# cpu.net
KiCad netlist of a schematic drawn in Altium Designer
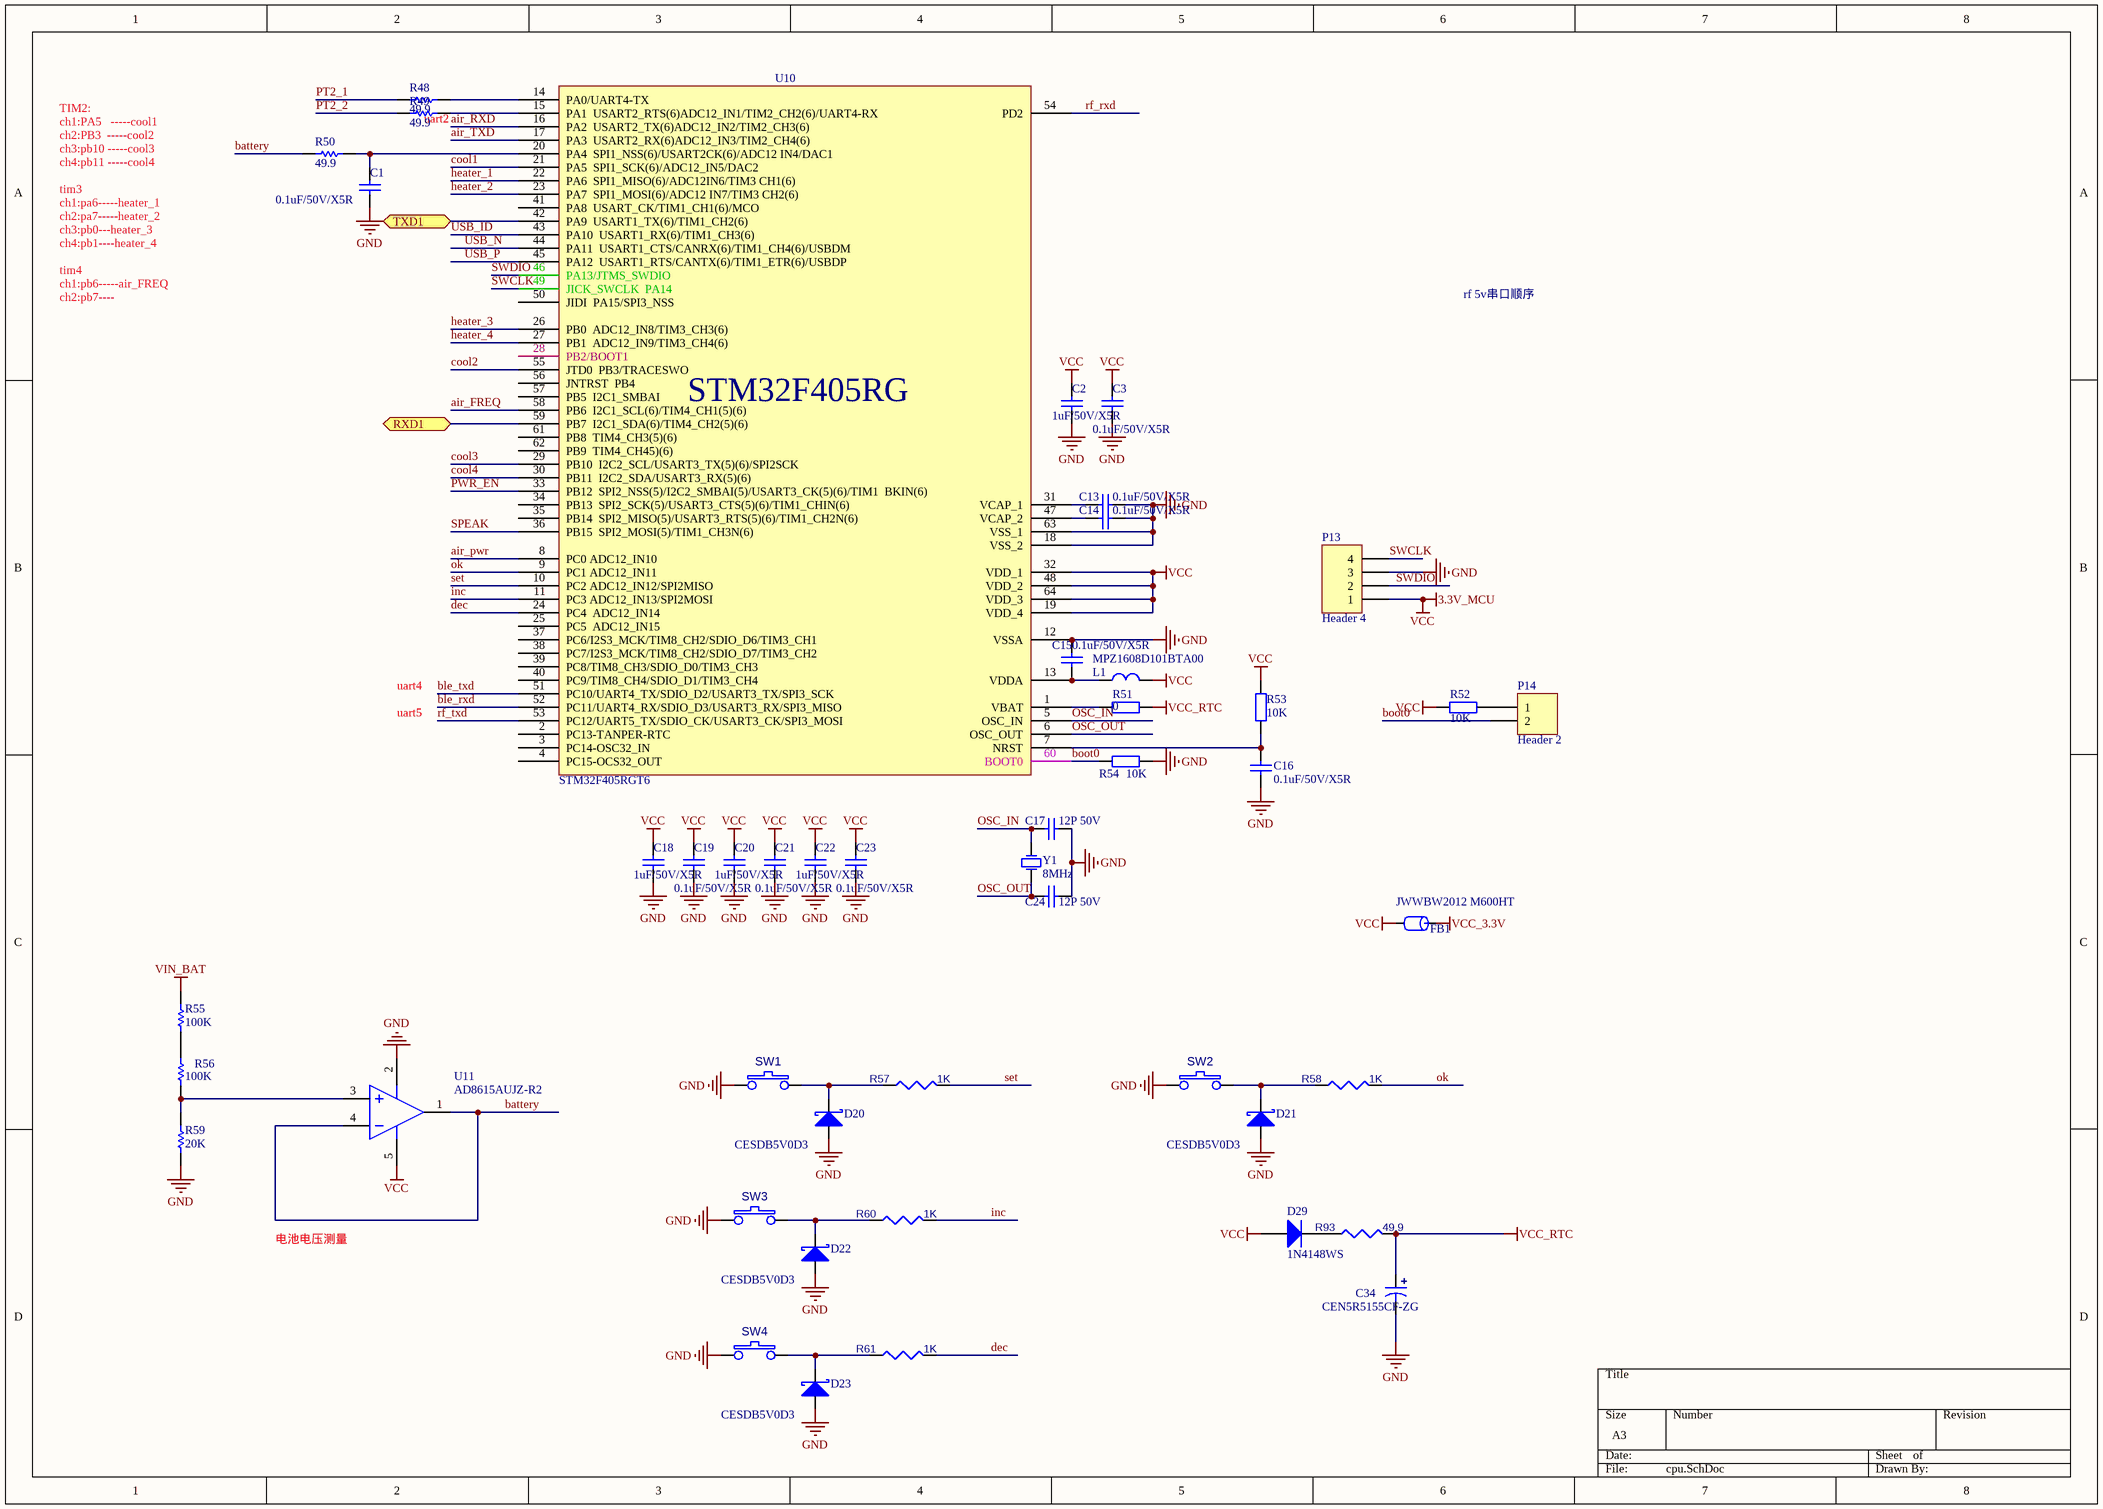
[diagram p0: cpu.SchDoc]

(export (version "E")
  (design (tool "Eeschema 10.0.6"))
  (components
    (comp (ref "C1")
      (value "0.1uF/50V/X5R")
      (footprint "0603C")
      (description "贴片电容 20%")
      (libsource (lib "XiaoyI") (part "CAP4"))
    )
    (comp (ref "C2")
      (value "1uF/50V/X5R")
      (footprint "0603C")
      (description "贴片电容 20%")
      (libsource (lib "XiaoyI") (part "CAP4"))
    )
    (comp (ref "C3")
      (value "0.1uF/50V/X5R")
      (footprint "0603C")
      (description "贴片电容 20%")
      (libsource (lib "XiaoyI") (part "CAP4"))
    )
    (comp (ref "C13")
      (value "0.1uF/50V/X5R")
      (footprint "0603C")
      (description "贴片电容 20%")
      (libsource (lib "XiaoyI") (part "CAP4"))
    )
    (comp (ref "C14")
      (value "0.1uF/50V/X5R")
      (footprint "0603C")
      (description "贴片电容 20%")
      (libsource (lib "XiaoyI") (part "CAP4"))
    )
    (comp (ref "C15")
      (value "0.1uF/50V/X5R")
      (footprint "0603C")
      (description "贴片电容 20%")
      (libsource (lib "XiaoyI") (part "CAP4"))
    )
    (comp (ref "C16")
      (value "0.1uF/50V/X5R")
      (footprint "0603C")
      (description "贴片电容 20%")
      (libsource (lib "XiaoyI") (part "CAP4"))
    )
    (comp (ref "C17")
      (value "12P 50V")
      (footprint "0603C")
      (description "贴片电容 20%")
      (libsource (lib "XiaoyI") (part "CAP4"))
    )
    (comp (ref "C18")
      (value "1uF/50V/X5R")
      (footprint "0603C")
      (description "贴片电容 20%")
      (libsource (lib "XiaoyI") (part "CAP4"))
    )
    (comp (ref "C19")
      (value "0.1uF/50V/X5R")
      (footprint "0603C")
      (description "贴片电容 20%")
      (libsource (lib "XiaoyI") (part "CAP4"))
    )
    (comp (ref "C20")
      (value "1uF/50V/X5R")
      (footprint "0603C")
      (description "贴片电容 20%")
      (libsource (lib "XiaoyI") (part "CAP4"))
    )
    (comp (ref "C21")
      (value "0.1uF/50V/X5R")
      (footprint "0603C")
      (description "贴片电容 20%")
      (libsource (lib "XiaoyI") (part "CAP4"))
    )
    (comp (ref "C22")
      (value "1uF/50V/X5R")
      (footprint "0603C")
      (description "贴片电容 20%")
      (libsource (lib "XiaoyI") (part "CAP4"))
    )
    (comp (ref "C23")
      (value "0.1uF/50V/X5R")
      (footprint "0603C")
      (description "贴片电容 20%")
      (libsource (lib "XiaoyI") (part "CAP4"))
    )
    (comp (ref "C24")
      (value "12P 50V")
      (footprint "0603C")
      (description "贴片电容 20%")
      (libsource (lib "XiaoyI") (part "CAP4"))
    )
    (comp (ref "C34")
      (value "CEN5R5155CF-ZG")
      (footprint "CAP-TH_BD21.0-P5.00-D0.8_CENXXX-CF")
      (description "电解电容")
      (libsource (lib "XiaoyI") (part "CAP2"))
    )
    (comp (ref "D20")
      (value "CESDB5V0D3")
      (footprint "SOD323")
      (description "Schottky Diode")
      (libsource (lib "*") (part "DIODE S"))
    )
    (comp (ref "D21")
      (value "CESDB5V0D3")
      (footprint "SOD323")
      (description "Schottky Diode")
      (libsource (lib "*") (part "DIODE S"))
    )
    (comp (ref "D22")
      (value "CESDB5V0D3")
      (footprint "SOD323")
      (description "Schottky Diode")
      (libsource (lib "*") (part "DIODE S"))
    )
    (comp (ref "D23")
      (value "CESDB5V0D3")
      (footprint "SOD323")
      (description "Schottky Diode")
      (libsource (lib "*") (part "DIODE S"))
    )
    (comp (ref "D29") (value "1N4148WS") (footprint "SOD323") (libsource (lib "Sch_library") (part "DIODE")))
    (comp (ref "FB1")
      (value "JWWBW2012 M600HT")
      (footprint "0805CZ")
      (libsource (lib "Schlib_20110825") (part "FB"))
    )
    (comp (ref "L1")
      (value "MPZ1608D101BTA00")
      (footprint "0603R")
      (description "磁珠电感 100R 100MHz")
      (libsource (lib "XiaoyI") (part "CIZHU1"))
    )
    (comp (ref "P13")
      (value "Header 4")
      (footprint "HDR1X4")
      (description "Header, 4-Pin")
      (fields (field (name "PUBLISHER") "Altium Limited"))
      (libsource (lib "Miscellaneous Connectors") (part "Header 4"))
    )
    (comp (ref "P14")
      (value "Header 2")
      (footprint "HDR1X2")
      (description "Header, 2-Pin")
      (fields (field (name "PUBLISHER") "Altium Limited"))
      (libsource (lib "Miscellaneous Connectors") (part "Header 2"))
    )
    (comp (ref "R48")
      (value "49.9")
      (footprint "0603R")
      (description "Resistor")
      (fields (field (name "PUBLISHER") "Altium Limited"))
      (libsource (lib "Miscellaneous Devices") (part "Res1"))
    )
    (comp (ref "R49")
      (value "49.9")
      (footprint "0603R")
      (description "Resistor")
      (fields (field (name "PUBLISHER") "Altium Limited"))
      (libsource (lib "Miscellaneous Devices") (part "Res1"))
    )
    (comp (ref "R50")
      (value "49.9")
      (footprint "0603R")
      (description "Resistor")
      (fields (field (name "PUBLISHER") "Altium Limited"))
      (libsource (lib "Miscellaneous Devices") (part "Res1"))
    )
    (comp (ref "R51")
      (value "0")
      (footprint "0603R")
      (description "贴片电阻 5%")
      (libsource (lib "XiaoyI") (part "RES2"))
    )
    (comp (ref "R52")
      (value "10K")
      (footprint "0603R")
      (description "贴片电阻 5%")
      (libsource (lib "XiaoyI") (part "RES2"))
    )
    (comp (ref "R53")
      (value "10K")
      (footprint "0603R")
      (description "贴片电阻 5%")
      (libsource (lib "") (part "RES2_2"))
    )
    (comp (ref "R54")
      (value "10K")
      (footprint "0603R")
      (description "贴片电阻 5%")
      (libsource (lib "") (part "RES2_1"))
    )
    (comp (ref "R55")
      (value "100K")
      (footprint "0603R")
      (description "Resistor")
      (fields (field (name "PUBLISHER") "Altium Limited"))
      (libsource (lib "Miscellaneous Devices") (part "Res1"))
    )
    (comp (ref "R56")
      (value "100K")
      (footprint "0603R")
      (description "Resistor")
      (fields (field (name "PUBLISHER") "Altium Limited"))
      (libsource (lib "Miscellaneous Devices") (part "Res1"))
    )
    (comp (ref "R57")
      (value "1K")
      (footprint "0603R")
      (fields (field (name "Comment") "1k/1%"))
      (libsource (lib "*") (part "RESISTOR_0"))
    )
    (comp (ref "R58")
      (value "1K")
      (footprint "0603R")
      (fields (field (name "Comment") "1k/1%"))
      (libsource (lib "*") (part "RESISTOR_0"))
    )
    (comp (ref "R59")
      (value "20K")
      (footprint "0603R")
      (description "Resistor")
      (fields (field (name "PUBLISHER") "Altium Limited"))
      (libsource (lib "Miscellaneous Devices") (part "Res1"))
    )
    (comp (ref "R60")
      (value "1K")
      (footprint "0603R")
      (fields (field (name "Comment") "1k/1%"))
      (libsource (lib "*") (part "RESISTOR_0"))
    )
    (comp (ref "R61")
      (value "1K")
      (footprint "0603R")
      (fields (field (name "Comment") "1k/1%"))
      (libsource (lib "*") (part "RESISTOR_0"))
    )
    (comp (ref "R93")
      (value "49.9")
      (footprint "0603R")
      (fields (field (name "Comment") "1k/1%"))
      (libsource (lib "*") (part "RESISTOR_0"))
    )
    (comp (ref "SW1")
      (value "SW PUSHBUTTON")
      (footprint "SW-SMD_L3.9-W3.0-P4.45")
      (libsource (lib "*") (part "SW PUSHBUTTON"))
    )
    (comp (ref "SW2")
      (value "SW PUSHBUTTON")
      (footprint "SW-SMD_L3.9-W3.0-P4.45")
      (libsource (lib "*") (part "SW PUSHBUTTON"))
    )
    (comp (ref "SW3")
      (value "SW PUSHBUTTON")
      (footprint "SW-SMD_L3.9-W3.0-P4.45")
      (libsource (lib "*") (part "SW PUSHBUTTON"))
    )
    (comp (ref "SW4")
      (value "SW PUSHBUTTON")
      (footprint "SW-SMD_L3.9-W3.0-P4.45")
      (libsource (lib "*") (part "SW PUSHBUTTON"))
    )
    (comp (ref "U10")
      (value "STM32F405RGT6")
      (footprint "LQFP-64")
      (description "MCU")
      (libsource (lib "XiaoyI") (part "STM32F405RG"))
    )
    (comp (ref "U11")
      (value "AD8615AUJZ-R2")
      (footprint "sot-23-5")
      (libsource (lib "Schlib1") (part "AD8615"))
    )
    (comp (ref "Y1")
      (value "8MHz")
      (footprint "CRAY_5032")
      (description "晶振")
      (libsource (lib "XiaoyI") (part "XTAL"))
    )
  )
  (nets
    (net (code "1") (name "/OSC_IN") (class "Default")
      (node (ref "C17") (pin "2") (pinfunction "2_2") (pintype "passive"))
      (node (ref "U10") (pin "5") (pinfunction "OSC_IN_5") (pintype "passive"))
      (node (ref "Y1") (pin "2") (pinfunction "OSC2_2") (pintype "passive"))
    )
    (net (code "2") (name "/OSC_OUT") (class "Default")
      (node (ref "C24") (pin "2") (pinfunction "2_2") (pintype "passive"))
      (node (ref "U10") (pin "6") (pinfunction "OSC_OUT_6") (pintype "passive"))
      (node (ref "Y1") (pin "1") (pinfunction "OSC1_1") (pintype "passive"))
    )
    (net (code "3") (name "/PT2_1") (class "Default")
      (node (ref "R48") (pin "1") (pinfunction "1_1") (pintype "passive"))
    )
    (net (code "4") (name "/PT2_2") (class "Default")
      (node (ref "R49") (pin "1") (pinfunction "1_1") (pintype "passive"))
    )
    (net (code "5") (name "/PWR_EN") (class "Default")
      (node (ref "U10") (pin "33") (pinfunction "PB12__SPI2_NSS(5)/I2C2_SMBAI(5)/USART3_CK(5)(6)/TIM1__BKIN(6)_33") (pintype "passive"))
    )
    (net (code "6") (name "/RXD1") (class "Default")
      (node (ref "U10") (pin "59") (pinfunction "PB7__I2C1_SDA(6)/TIM4_CH2(5)(6)_59") (pintype "passive"))
    )
    (net (code "7") (name "/SPEAK") (class "Default")
      (node (ref "U10") (pin "36") (pinfunction "PB15__SPI2_MOSI(5)/TIM1_CH3N(6)_36") (pintype "passive"))
    )
    (net (code "8") (name "/SWCLK") (class "Default")
      (node (ref "P13") (pin "4") (pinfunction "4_4") (pintype "passive"))
      (node (ref "U10") (pin "49") (pinfunction "JICK_SWCLK__PA14_49") (pintype "passive"))
    )
    (net (code "9") (name "/SWDIO") (class "Default")
      (node (ref "P13") (pin "2") (pinfunction "2_2") (pintype "passive"))
      (node (ref "U10") (pin "46") (pinfunction "PA13/JTMS_SWDIO_46") (pintype "passive"))
    )
    (net (code "10") (name "/TXD1") (class "Default")
      (node (ref "U10") (pin "42") (pinfunction "PA9__USART1_TX(6)/TIM1_CH2(6)_42") (pintype "passive"))
    )
    (net (code "11") (name "/USB_ID") (class "Default")
      (node (ref "U10") (pin "43") (pinfunction "PA10__USART1_RX(6)/TIM1_CH3(6)_43") (pintype "passive"))
    )
    (net (code "12") (name "/USB_N") (class "Default")
      (node (ref "U10") (pin "44") (pinfunction "PA11__USART1_CTS/CANRX(6)/TIM1_CH4(6)/USBDM_44") (pintype "passive"))
    )
    (net (code "13") (name "/USB_P") (class "Default")
      (node (ref "U10") (pin "45") (pinfunction "PA12__USART1_RTS/CANTX(6)/TIM1_ETR(6)/USBDP_45") (pintype "passive"))
    )
    (net (code "14") (name "/air_FREQ") (class "Default")
      (node (ref "U10") (pin "58") (pinfunction "PB6__I2C1_SCL(6)/TIM4_CH1(5)(6)_58") (pintype "passive"))
    )
    (net (code "15") (name "/air_RXD") (class "Default")
      (node (ref "U10") (pin "16") (pinfunction "PA2__USART2_TX(6)ADC12_IN2/TIM2_CH3(6)_16") (pintype "passive"))
    )
    (net (code "16") (name "/air_TXD") (class "Default")
      (node (ref "U10") (pin "17") (pinfunction "PA3__USART2_RX(6)ADC12_IN3/TIM2_CH4(6)_17") (pintype "passive"))
    )
    (net (code "17") (name "/air_pwr") (class "Default")
      (node (ref "U10") (pin "8") (pinfunction "PC0_ADC12_IN10_8") (pintype "passive"))
    )
    (net (code "18") (name "/battery") (class "Default")
      (node (ref "R50") (pin "1") (pinfunction "1_1") (pintype "passive"))
      (node (ref "U11") (pin "1") (pinfunction "OS_NUL_1") (pintype "passive"))
      (node (ref "U11") (pin "4") (pinfunction "V-_4") (pintype "power_in"))
    )
    (net (code "19") (name "/ble_rxd") (class "Default")
      (node (ref "U10") (pin "52") (pinfunction "PC11/UART4_RX/SDIO_D3/USART3_RX/SPI3_MISO_52") (pintype "passive"))
    )
    (net (code "20") (name "/ble_txd") (class "Default")
      (node (ref "U10") (pin "51") (pinfunction "PC10/UART4_TX/SDIO_D2/USART3_TX/SPI3_SCK_51") (pintype "passive"))
    )
    (net (code "21") (name "/boot0") (class "Default")
      (node (ref "P14") (pin "2") (pinfunction "2_2") (pintype "passive"))
      (node (ref "R54") (pin "1") (pinfunction "1_1") (pintype "passive"))
      (node (ref "U10") (pin "60") (pinfunction "BOOT0_60") (pintype "passive"))
    )
    (net (code "22") (name "/cool1") (class "Default")
      (node (ref "U10") (pin "21") (pinfunction "PA5__SPI1_SCK(6)/ADC12_IN5/DAC2_21") (pintype "passive"))
    )
    (net (code "23") (name "/cool2") (class "Default")
      (node (ref "U10") (pin "55") (pinfunction "JTD0__PB3/TRACESWO_55") (pintype "passive"))
    )
    (net (code "24") (name "/cool3") (class "Default")
      (node (ref "U10") (pin "29") (pinfunction "PB10__I2C2_SCL/USART3_TX(5)(6)/SPI2SCK_29") (pintype "passive"))
    )
    (net (code "25") (name "/cool4") (class "Default")
      (node (ref "U10") (pin "30") (pinfunction "PB11__I2C2_SDA/USART3_RX(5)(6)_30") (pintype "passive"))
    )
    (net (code "26") (name "/dec") (class "Default")
      (node (ref "R61") (pin "2") (pinfunction "2_2") (pintype "passive"))
      (node (ref "U10") (pin "24") (pinfunction "PC4__ADC12_IN14_24") (pintype "passive"))
    )
    (net (code "27") (name "/heater_1") (class "Default")
      (node (ref "U10") (pin "22") (pinfunction "PA6__SPI1_MISO(6)/ADC12IN6/TIM3_CH1(6)_22") (pintype "passive"))
    )
    (net (code "28") (name "/heater_2") (class "Default")
      (node (ref "U10") (pin "23") (pinfunction "PA7__SPI1_MOSI(6)/ADC12_IN7/TIM3_CH2(6)_23") (pintype "passive"))
    )
    (net (code "29") (name "/heater_3") (class "Default")
      (node (ref "U10") (pin "26") (pinfunction "PB0__ADC12_IN8/TIM3_CH3(6)_26") (pintype "passive"))
    )
    (net (code "30") (name "/heater_4") (class "Default")
      (node (ref "U10") (pin "27") (pinfunction "PB1__ADC12_IN9/TIM3_CH4(6)_27") (pintype "passive"))
    )
    (net (code "31") (name "/inc") (class "Default")
      (node (ref "R60") (pin "2") (pinfunction "2_2") (pintype "passive"))
      (node (ref "U10") (pin "11") (pinfunction "PC3_ADC12_IN13/SPI2MOSI_11") (pintype "passive"))
    )
    (net (code "32") (name "/ok") (class "Default")
      (node (ref "R58") (pin "2") (pinfunction "2_2") (pintype "passive"))
      (node (ref "U10") (pin "9") (pinfunction "PC1_ADC12_IN11_9") (pintype "passive"))
    )
    (net (code "33") (name "/rf_rxd") (class "Default")
      (node (ref "U10") (pin "54") (pinfunction "PD2_54") (pintype "passive"))
    )
    (net (code "34") (name "/rf_txd") (class "Default")
      (node (ref "U10") (pin "53") (pinfunction "PC12/UART5_TX/SDIO_CK/USART3_CK/SPI3_MOSI_53") (pintype "passive"))
    )
    (net (code "35") (name "/set") (class "Default")
      (node (ref "R57") (pin "2") (pinfunction "2_2") (pintype "passive"))
      (node (ref "U10") (pin "10") (pinfunction "PC2_ADC12_IN12/SPI2MISO_10") (pintype "passive"))
    )
    (net (code "36") (name "3.3V_MCU") (class "Default")
      (node (ref "C18") (pin "2") (pinfunction "2_2") (pintype "passive"))
      (node (ref "C19") (pin "2") (pinfunction "2_2") (pintype "passive"))
      (node (ref "C2") (pin "2") (pinfunction "2_2") (pintype "passive"))
      (node (ref "C20") (pin "2") (pinfunction "2_2") (pintype "passive"))
      (node (ref "C21") (pin "2") (pinfunction "2_2") (pintype "passive"))
      (node (ref "C22") (pin "2") (pinfunction "2_2") (pintype "passive"))
      (node (ref "C23") (pin "2") (pinfunction "2_2") (pintype "passive"))
      (node (ref "C3") (pin "2") (pinfunction "2_2") (pintype "passive"))
      (node (ref "D29") (pin "1") (pinfunction "A_1") (pintype "passive"))
      (node (ref "FB1") (pin "2") (pintype "passive"))
      (node (ref "L1") (pin "2") (pinfunction "2_2") (pintype "passive"))
      (node (ref "P13") (pin "1") (pinfunction "1_1") (pintype "passive"))
      (node (ref "R52") (pin "2") (pinfunction "2_2") (pintype "passive"))
      (node (ref "R53") (pin "1") (pinfunction "1_1") (pintype "passive"))
      (node (ref "U10") (pin "19") (pinfunction "VDD_4_19") (pintype "passive"))
      (node (ref "U10") (pin "32") (pinfunction "VDD_1_32") (pintype "passive"))
      (node (ref "U10") (pin "48") (pinfunction "VDD_2_48") (pintype "passive"))
      (node (ref "U10") (pin "64") (pinfunction "VDD_3_64") (pintype "passive"))
      (node (ref "U11") (pin "5") (pinfunction "VCC_5") (pintype "passive"))
    )
    (net (code "37") (name "GND") (class "Default")
      (node (ref "C1") (pin "1") (pinfunction "1_1") (pintype "passive"))
      (node (ref "C13") (pin "1") (pinfunction "1_1") (pintype "passive"))
      (node (ref "C14") (pin "1") (pinfunction "1_1") (pintype "passive"))
      (node (ref "C15") (pin "1") (pinfunction "1_1") (pintype "passive"))
      (node (ref "C16") (pin "1") (pinfunction "1_1") (pintype "passive"))
      (node (ref "C17") (pin "1") (pinfunction "1_1") (pintype "passive"))
      (node (ref "C18") (pin "1") (pinfunction "1_1") (pintype "passive"))
      (node (ref "C19") (pin "1") (pinfunction "1_1") (pintype "passive"))
      (node (ref "C2") (pin "1") (pinfunction "1_1") (pintype "passive"))
      (node (ref "C20") (pin "1") (pinfunction "1_1") (pintype "passive"))
      (node (ref "C21") (pin "1") (pinfunction "1_1") (pintype "passive"))
      (node (ref "C22") (pin "1") (pinfunction "1_1") (pintype "passive"))
      (node (ref "C23") (pin "1") (pinfunction "1_1") (pintype "passive"))
      (node (ref "C24") (pin "1") (pinfunction "1_1") (pintype "passive"))
      (node (ref "C3") (pin "1") (pinfunction "1_1") (pintype "passive"))
      (node (ref "C34") (pin "2") (pinfunction "2_2") (pintype "passive"))
      (node (ref "D20") (pin "1") (pinfunction "A_1") (pintype "passive"))
      (node (ref "D21") (pin "1") (pinfunction "A_1") (pintype "passive"))
      (node (ref "D22") (pin "1") (pinfunction "A_1") (pintype "passive"))
      (node (ref "D23") (pin "1") (pinfunction "A_1") (pintype "passive"))
      (node (ref "P13") (pin "3") (pinfunction "3_3") (pintype "passive"))
      (node (ref "R54") (pin "2") (pinfunction "2_2") (pintype "passive"))
      (node (ref "R59") (pin "2") (pinfunction "2_2") (pintype "passive"))
      (node (ref "SW1") (pin "1") (pinfunction "1_1") (pintype "passive"))
      (node (ref "SW2") (pin "1") (pinfunction "1_1") (pintype "passive"))
      (node (ref "SW3") (pin "1") (pinfunction "1_1") (pintype "passive"))
      (node (ref "SW4") (pin "1") (pinfunction "1_1") (pintype "passive"))
      (node (ref "U10") (pin "12") (pinfunction "VSSA_12") (pintype "passive"))
      (node (ref "U10") (pin "18") (pinfunction "VSS_2_18") (pintype "passive"))
      (node (ref "U10") (pin "63") (pinfunction "VSS_1_63") (pintype "passive"))
      (node (ref "U11") (pin "2") (pinfunction "G_2") (pintype "power_in"))
    )
    (net (code "38") (name "Net-(D20-K)") (class "Default")
      (node (ref "D20") (pin "2") (pinfunction "K_2") (pintype "passive"))
      (node (ref "R57") (pin "1") (pinfunction "1_1") (pintype "passive"))
      (node (ref "SW1") (pin "2") (pinfunction "2_2") (pintype "passive"))
    )
    (net (code "39") (name "Net-(D21-K)") (class "Default")
      (node (ref "D21") (pin "2") (pinfunction "K_2") (pintype "passive"))
      (node (ref "R58") (pin "1") (pinfunction "1_1") (pintype "passive"))
      (node (ref "SW2") (pin "2") (pinfunction "2_2") (pintype "passive"))
    )
    (net (code "40") (name "Net-(D22-K)") (class "Default")
      (node (ref "D22") (pin "2") (pinfunction "K_2") (pintype "passive"))
      (node (ref "R60") (pin "1") (pinfunction "1_1") (pintype "passive"))
      (node (ref "SW3") (pin "2") (pinfunction "2_2") (pintype "passive"))
    )
    (net (code "41") (name "Net-(D23-K)") (class "Default")
      (node (ref "D23") (pin "2") (pinfunction "K_2") (pintype "passive"))
      (node (ref "R61") (pin "1") (pinfunction "1_1") (pintype "passive"))
      (node (ref "SW4") (pin "2") (pinfunction "2_2") (pintype "passive"))
    )
    (net (code "42") (name "Net-(D29-K)") (class "Default")
      (node (ref "D29") (pin "2") (pinfunction "K_2") (pintype "passive"))
      (node (ref "R93") (pin "1") (pinfunction "1_1") (pintype "passive"))
    )
    (net (code "43") (name "Net-(P14-Pad1)") (class "Default")
      (node (ref "P14") (pin "1") (pinfunction "1_1") (pintype "passive"))
      (node (ref "R52") (pin "1") (pinfunction "1_1") (pintype "passive"))
    )
    (net (code "44") (name "Net-(R55-Pad2)") (class "Default")
      (node (ref "R55") (pin "2") (pinfunction "2_2") (pintype "passive"))
      (node (ref "R56") (pin "1") (pinfunction "1_1") (pintype "passive"))
    )
    (net (code "45") (name "Net-(U10-NRST)") (class "Default")
      (node (ref "C16") (pin "2") (pinfunction "2_2") (pintype "passive"))
      (node (ref "R53") (pin "2") (pinfunction "2_2") (pintype "passive"))
      (node (ref "U10") (pin "7") (pinfunction "NRST_7") (pintype "passive"))
    )
    (net (code "46") (name "Net-(U10-PA0{slash}UART4-TX)") (class "Default")
      (node (ref "R48") (pin "2") (pinfunction "2_2") (pintype "passive"))
      (node (ref "U10") (pin "14") (pinfunction "PA0/UART4-TX_14") (pintype "passive"))
    )
    (net (code "47") (name "Net-(U10-PA1__USART2_RTS(6)ADC12_IN1{slash}TIM2_CH2(6){slash}UART4-RX)") (class "Default")
      (node (ref "R49") (pin "2") (pinfunction "2_2") (pintype "passive"))
      (node (ref "U10") (pin "15") (pinfunction "PA1__USART2_RTS(6)ADC12_IN1/TIM2_CH2(6)/UART4-RX_15") (pintype "passive"))
    )
    (net (code "48") (name "Net-(U10-PA4__SPI1_NSS(6){slash}USART2CK(6){slash}ADC12_IN4{slash}DAC1)") (class "Default")
      (node (ref "C1") (pin "2") (pinfunction "2_2") (pintype "passive"))
      (node (ref "R50") (pin "2") (pinfunction "2_2") (pintype "passive"))
      (node (ref "U10") (pin "20") (pinfunction "PA4__SPI1_NSS(6)/USART2CK(6)/ADC12_IN4/DAC1_20") (pintype "passive"))
    )
    (net (code "49") (name "Net-(U10-VBAT)") (class "Default")
      (node (ref "R51") (pin "2") (pinfunction "2_2") (pintype "passive"))
      (node (ref "U10") (pin "1") (pinfunction "VBAT_1") (pintype "passive"))
    )
    (net (code "50") (name "Net-(U10-VCAP_1)") (class "Default")
      (node (ref "C13") (pin "2") (pinfunction "2_2") (pintype "passive"))
      (node (ref "U10") (pin "31") (pinfunction "VCAP_1_31") (pintype "passive"))
    )
    (net (code "51") (name "Net-(U10-VCAP_2)") (class "Default")
      (node (ref "C14") (pin "2") (pinfunction "2_2") (pintype "passive"))
      (node (ref "U10") (pin "47") (pinfunction "VCAP_2_47") (pintype "passive"))
    )
    (net (code "52") (name "Net-(U10-VDDA)") (class "Default")
      (node (ref "C15") (pin "2") (pinfunction "2_2") (pintype "passive"))
      (node (ref "L1") (pin "1") (pinfunction "1_1") (pintype "passive"))
      (node (ref "U10") (pin "13") (pinfunction "VDDA_13") (pintype "passive"))
    )
    (net (code "53") (name "Net-(U11-V+)") (class "Default")
      (node (ref "R56") (pin "2") (pinfunction "2_2") (pintype "passive"))
      (node (ref "R59") (pin "1") (pinfunction "1_1") (pintype "passive"))
      (node (ref "U11") (pin "3") (pinfunction "V+_3") (pintype "power_in"))
    )
    (net (code "54") (name "VCC_3.3V") (class "Default") (node (ref "FB1") (pin "1") (pintype "passive")))
    (net (code "55") (name "VCC_RTC") (class "Default")
      (node (ref "C34") (pin "1") (pinfunction "1_1") (pintype "passive"))
      (node (ref "R51") (pin "1") (pinfunction "1_1") (pintype "passive"))
      (node (ref "R93") (pin "2") (pinfunction "2_2") (pintype "passive"))
    )
    (net (code "56") (name "VIN_BAT") (class "Default")
      (node (ref "R55") (pin "1") (pinfunction "1_1") (pintype "passive"))
    )
    (net (code "57") (name "unconnected-(U10-JIDI__PA15{slash}SPI3_NSS-Pad50)") (class "Default")
      (node (ref "U10") (pin "50") (pinfunction "JIDI__PA15/SPI3_NSS_50") (pintype "passive"))
    )
    (net (code "58") (name "unconnected-(U10-JNTRST__PB4-Pad56)") (class "Default")
      (node (ref "U10") (pin "56") (pinfunction "JNTRST__PB4_56") (pintype "passive"))
    )
    (net (code "59") (name "unconnected-(U10-PA8__USART_CK{slash}TIM1_CH1(6){slash}MCO-Pad41)") (class "Default")
      (node (ref "U10") (pin "41") (pinfunction "PA8__USART_CK/TIM1_CH1(6)/MCO_41") (pintype "passive"))
    )
    (net (code "60") (name "unconnected-(U10-PB2{slash}BOOT1-Pad28)") (class "Default")
      (node (ref "U10") (pin "28") (pinfunction "PB2/BOOT1_28") (pintype "passive"))
    )
    (net (code "61") (name "unconnected-(U10-PB5__I2C1_SMBAI-Pad57)") (class "Default")
      (node (ref "U10") (pin "57") (pinfunction "PB5__I2C1_SMBAI_57") (pintype "passive"))
    )
    (net (code "62") (name "unconnected-(U10-PB8__TIM4_CH3(5)(6)-Pad61)") (class "Default")
      (node (ref "U10") (pin "61") (pinfunction "PB8__TIM4_CH3(5)(6)_61") (pintype "passive"))
    )
    (net (code "63") (name "unconnected-(U10-PB9__TIM4_CH45)(6)-Pad62)") (class "Default")
      (node (ref "U10") (pin "62") (pinfunction "PB9__TIM4_CH45)(6)_62") (pintype "passive"))
    )
    (net (code "64") (name "unconnected-(U10-PB13__SPI2_SCK(5){slash}USART3_CTS(5)(6){slash}TIM1_CHIN(6)-Pad34)") (class "Default")
      (node (ref "U10") (pin "34") (pinfunction "PB13__SPI2_SCK(5)/USART3_CTS(5)(6)/TIM1_CHIN(6)_34") (pintype "passive"))
    )
    (net (code "65") (name "unconnected-(U10-PB14__SPI2_MISO(5){slash}USART3_RTS(5)(6){slash}TIM1_CH2N(6)-Pad35)") (class "Default")
      (node (ref "U10") (pin "35") (pinfunction "PB14__SPI2_MISO(5)/USART3_RTS(5)(6)/TIM1_CH2N(6)_35") (pintype "passive"))
    )
    (net (code "66") (name "unconnected-(U10-PC5__ADC12_IN15-Pad25)") (class "Default")
      (node (ref "U10") (pin "25") (pinfunction "PC5__ADC12_IN15_25") (pintype "passive"))
    )
    (net (code "67") (name "unconnected-(U10-PC6{slash}I2S3_MCK{slash}TIM8_CH2{slash}SDIO_D6{slash}TIM3_CH1-Pad37)") (class "Default")
      (node (ref "U10") (pin "37") (pinfunction "PC6/I2S3_MCK/TIM8_CH2/SDIO_D6/TIM3_CH1_37") (pintype "passive"))
    )
    (net (code "68") (name "unconnected-(U10-PC7{slash}I2S3_MCK{slash}TIM8_CH2{slash}SDIO_D7{slash}TIM3_CH2-Pad38)") (class "Default")
      (node (ref "U10") (pin "38") (pinfunction "PC7/I2S3_MCK/TIM8_CH2/SDIO_D7/TIM3_CH2_38") (pintype "passive"))
    )
    (net (code "69") (name "unconnected-(U10-PC8{slash}TIM8_CH3{slash}SDIO_D0{slash}TIM3_CH3-Pad39)") (class "Default")
      (node (ref "U10") (pin "39") (pinfunction "PC8/TIM8_CH3/SDIO_D0/TIM3_CH3_39") (pintype "passive"))
    )
    (net (code "70") (name "unconnected-(U10-PC9{slash}TIM8_CH4{slash}SDIO_D1{slash}TIM3_CH4-Pad40)") (class "Default")
      (node (ref "U10") (pin "40") (pinfunction "PC9/TIM8_CH4/SDIO_D1/TIM3_CH4_40") (pintype "passive"))
    )
    (net (code "71") (name "unconnected-(U10-PC13-TANPER-RTC-Pad2)") (class "Default")
      (node (ref "U10") (pin "2") (pinfunction "PC13-TANPER-RTC_2") (pintype "passive"))
    )
    (net (code "72") (name "unconnected-(U10-PC14-OSC32_IN-Pad3)") (class "Default")
      (node (ref "U10") (pin "3") (pinfunction "PC14-OSC32_IN_3") (pintype "passive"))
    )
    (net (code "73") (name "unconnected-(U10-PC15-OCS32_OUT-Pad4)") (class "Default")
      (node (ref "U10") (pin "4") (pinfunction "PC15-OCS32_OUT_4") (pintype "passive"))
    )
  )
)
